# GPS.net
KiCad netlist of a schematic drawn in Altium Designer
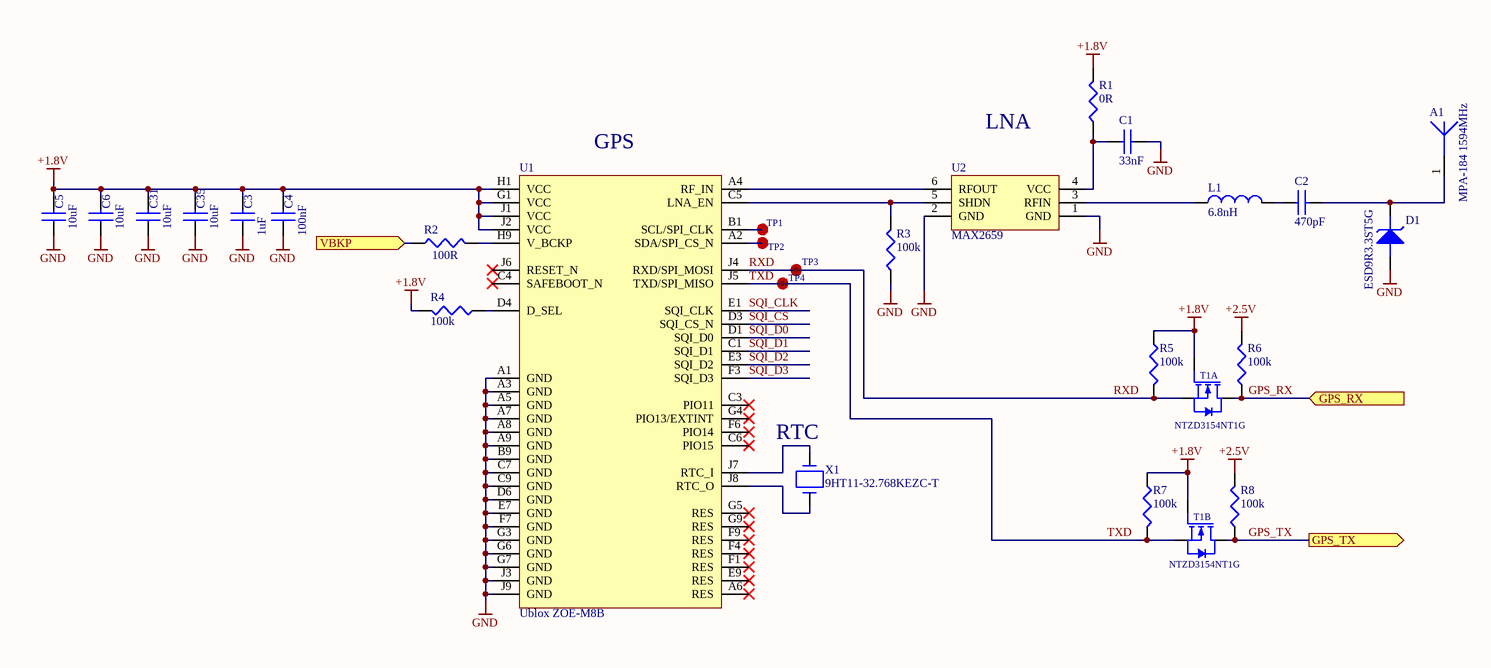
[diagram p0: GPS.SchDoc]

(export (version "E")
  (design (tool "Eeschema 10.0.6"))
  (components
    (comp (ref "A1")
      (value "MPA-184 1594MHz")
      (footprint "MPA-184")
      (description "Antennas Passive GPS/GLONASS Patch Antenna")
      (fields (field (name "MANUFACTURER") "Antenova") (field (name "MANUFACTURER PART NUMBER") "SR42I010-R"))
      (libsource (lib "Passive") (part "ANT - MAXTENA MPA-184 1594MHz"))
    )
    (comp (ref "C1")
      (value "33nF")
      (footprint "CAP0402")
      (fields
        (field (name "MANUFACTURER") "Multicomp")
        (field (name "MANUFACTURER PART NUMBER") "MC0402N330J160CT")
        (field (name "TOLERANCE") "5%")
      )
      (libsource (lib "Passive") (part "C - 33pF/0402"))
    )
    (comp (ref "C2")
      (value "470pF")
      (footprint "CAP0402")
      (fields
        (field (name "MANUFACTURER") "Murata")
        (field (name "MANUFACTURER PART NUMBER") "GRT155R71H471KE01D")
        (field (name "IRNAS PART NO.") "/")
      )
      (libsource (lib "Passive") (part "C - 470pF/0402"))
    )
    (comp (ref "C3")
      (value "1uF")
      (footprint "CAP0402")
      (description "CAP CER 1UF 10V 20% X5R 0402")
      (fields
        (field (name "MANUFACTURER") "Murata")
        (field (name "MANUFACTURER PART NUMBER") "GRM155R61A105ME15D")
      )
      (libsource (lib "Passive") (part "C - 1uF/0402"))
    )
    (comp (ref "C4")
      (value "100nF")
      (footprint "CAP0402")
      (fields
        (field (name "MANUFACTURER") "Multicomp")
        (field (name "MANUFACTURER PART NUMBER") "MC0402X104J160CT")
        (field (name "TOLERANCE") "5%")
      )
      (libsource (lib "Passive") (part "C - 100nF/0402"))
    )
    (comp (ref "C5")
      (value "10uF")
      (footprint "CAP0603")
      (description "10uf/0603/20%")
      (fields
        (field (name "MANUFACTURER") "KEMET")
        (field (name "MANUFACTURER PART NUMBER") "C0603C106M8PACTU")
      )
      (libsource (lib "pira-smart-schlib") (part "10uF"))
    )
    (comp (ref "C6")
      (value "10uF")
      (footprint "CAP0603")
      (description "10uf/0603/20%")
      (fields
        (field (name "MANUFACTURER") "KEMET")
        (field (name "MANUFACTURER PART NUMBER") "C0603C106M8PACTU")
      )
      (libsource (lib "pira-smart-schlib") (part "10uF"))
    )
    (comp (ref "C31")
      (value "10uF")
      (footprint "CAP0603")
      (description "10uf/0603/20%")
      (fields
        (field (name "MANUFACTURER") "KEMET")
        (field (name "MANUFACTURER PART NUMBER") "C0603C106M8PACTU")
      )
      (libsource (lib "pira-smart-schlib") (part "10uF"))
    )
    (comp (ref "C35")
      (value "10uF")
      (footprint "CAP0603")
      (description "10uf/0603/20%")
      (fields
        (field (name "MANUFACTURER") "KEMET")
        (field (name "MANUFACTURER PART NUMBER") "C0603C106M8PACTU")
      )
      (libsource (lib "pira-smart-schlib") (part "10uF"))
    )
    (comp (ref "D1")
      (value "ESD9R3.3ST5G")
      (footprint "SOD-923")
      (description "TVS Diode, ESD9R Series, Unidirectional, 3.3 V, 7.8 V")
      (fields
        (field (name "MANUFACTURER") "DIODES INC.")
        (field (name "MANUFACTURER PART NUMBER") "1N4148W-7-F.")
      )
      (libsource (lib "Active") (part "D_TVS - ESD9R3.3ST5G"))
    )
    (comp (ref "L1")
      (value "6.8nH")
      (footprint "IND0402")
      (description "FIXED IND 33NH 200MA 580 MOHM")
      (fields
        (field (name "MANUFACTURER") "Murata")
        (field (name "MANUFACTURER PART NUMBER") "LQG15HS33NJ02D")
      )
      (libsource (lib "Passive") (part "L - 33nH/0402"))
    )
    (comp (ref "R1")
      (value "0R")
      (footprint "RES0402")
      (description "RESISTOR, 0402, 0R, ANTI SULFURATION")
      (fields
        (field (name "MANUFACTURER") "Multicomp")
        (field (name "MANUFACTURER PART NUMBER") "MCMR04X000PTL")
      )
      (libsource (lib "Passive") (part "R - 0R/0402"))
    )
    (comp (ref "R2")
      (value "100R")
      (footprint "RES0402")
      (fields
        (field (name "MANUFACTURER") "Multicomp")
        (field (name "MANUFACTURER PART NUMBER") "MCMR04X1000FTL")
        (field (name "TOLERANCE") "1%")
      )
      (libsource (lib "Passive") (part "R - 100R/0402"))
    )
    (comp (ref "R3")
      (value "100k")
      (footprint "RES0402")
      (description "MULTICOMP   MCWR04X1003FTL   RES, THICK FILM, 100KOHM, 1%, 0.0625W")
      (fields
        (field (name "MANUFACTURER") "Multicomp")
        (field (name "MANUFACTURER PART NUMBER") "MCWR04X1003FTL")
      )
      (libsource (lib "Passive") (part "R - 100k/0402"))
    )
    (comp (ref "R4")
      (value "100k")
      (footprint "RES0402")
      (description "MULTICOMP   MCWR04X1003FTL   RES, THICK FILM, 100KOHM, 1%, 0.0625W")
      (fields
        (field (name "MANUFACTURER") "Multicomp")
        (field (name "MANUFACTURER PART NUMBER") "MCWR04X1003FTL")
      )
      (libsource (lib "Passive") (part "R - 100k/0402"))
    )
    (comp (ref "R5")
      (value "100k")
      (footprint "RES0402")
      (description "MULTICOMP   MCWR04X1003FTL   RES, THICK FILM, 100KOHM, 1%, 0.0625W")
      (fields
        (field (name "MANUFACTURER") "Multicomp")
        (field (name "MANUFACTURER PART NUMBER") "MCWR04X1003FTL")
      )
      (libsource (lib "Passive") (part "R - 100k/0402"))
    )
    (comp (ref "R6")
      (value "100k")
      (footprint "RES0402")
      (description "MULTICOMP   MCWR04X1003FTL   RES, THICK FILM, 100KOHM, 1%, 0.0625W")
      (fields
        (field (name "MANUFACTURER") "Multicomp")
        (field (name "MANUFACTURER PART NUMBER") "MCWR04X1003FTL")
      )
      (libsource (lib "Passive") (part "R - 100k/0402"))
    )
    (comp (ref "R7")
      (value "100k")
      (footprint "RES0402")
      (description "MULTICOMP   MCWR04X1003FTL   RES, THICK FILM, 100KOHM, 1%, 0.0625W")
      (fields
        (field (name "MANUFACTURER") "Multicomp")
        (field (name "MANUFACTURER PART NUMBER") "MCWR04X1003FTL")
      )
      (libsource (lib "Passive") (part "R - 100k/0402"))
    )
    (comp (ref "R8")
      (value "100k")
      (footprint "RES0402")
      (description "MULTICOMP   MCWR04X1003FTL   RES, THICK FILM, 100KOHM, 1%, 0.0625W")
      (fields
        (field (name "MANUFACTURER") "Multicomp")
        (field (name "MANUFACTURER PART NUMBER") "MCWR04X1003FTL")
      )
      (libsource (lib "Passive") (part "R - 100k/0402"))
    )
    (comp (ref "T1")
      (value "NTZD3154NT1G")
      (footprint "SOT-563")
      (description "Dual MOSFET, Dual N Channel, 540 mA, 20 V, 0.4 ohm, 4.5 V, 1 V")
      (fields (field (name "AUTHOR") "Ciril Golob"))
      (libsource (lib "Active") (part "T_M - NTZD3154NT1G"))
    )
    (comp (ref "TP1")
      (value "TestPoint")
      (footprint "Passive:TestPoint:1.2x1.2mm")
      (description "TEST POINT ROUND SMD")
      (libsource (lib "Passive") (part "TestPoint"))
    )
    (comp (ref "TP2")
      (value "TestPoint")
      (footprint "Passive:TestPoint:1.2x1.2mm")
      (description "TEST POINT ROUND SMD")
      (libsource (lib "Passive") (part "TestPoint"))
    )
    (comp (ref "TP3")
      (value "TestPoint")
      (footprint "Passive:TestPoint:1.2x1.2mm")
      (description "TEST POINT ROUND SMD")
      (libsource (lib "Passive") (part "TestPoint"))
    )
    (comp (ref "TP4")
      (value "TestPoint")
      (footprint "Passive:TestPoint:1.2x1.2mm")
      (description "TEST POINT ROUND SMD")
      (libsource (lib "Passive") (part "TestPoint"))
    )
    (comp (ref "U1")
      (value "Ublox ZOE-M8B")
      (footprint "S-LGA51")
      (description "ZOE-M8 RF Receiver BeiDou, Galileo, GLONASS, GNSS, GPS -160dBm")
      (fields (field (name "MANUFACTURER") "u-blox") (field (name "MANUFACTURER PART NUMBER") "MAX-M8Q-0"))
      (libsource (lib "Active") (part "RF - UBLOX-ZOE-M8B"))
    )
    (comp (ref "U2")
      (value "MAX2659")
      (footprint "uDFN-6")
      (description "RF Amplifier, GPS / GNSS, 20.5 dB Gain / 0.8 dB Noise, 1575.42 MHz, 1.6 V to 3.3 V Supply")
      (fields (field (name "MANUFACTURER") "u-blox") (field (name "MANUFACTURER PART NUMBER") "MAX-M8Q-0"))
      (libsource (lib "Active") (part "RF - MAX2659"))
    )
    (comp (ref "X1")
      (value "9HT11-32.768KEZC-T")
      (footprint "9HT11")
      (description "Crystal, 32.768 kHz, SMD, 2mm x 1.2mm, 9 pF, 10 ppm, 9HT11 Series")
      (fields (field (name "MANUFACTURER") "IQD") (field (name "MANUFACTURER PART NUMBER") "LFXTAL009678"))
      (libsource (lib "Passive") (part "X - 9HT11-32.768KEZC-T"))
    )
  )
  (nets
    (net (code "1") (name "+1.8V") (class "Default")
      (node (ref "C3") (pin "2") (pinfunction "2_2") (pintype "passive"))
      (node (ref "C31") (pin "2") (pinfunction "2_2") (pintype "passive"))
      (node (ref "C35") (pin "2") (pinfunction "2_2") (pintype "passive"))
      (node (ref "C4") (pin "2") (pinfunction "2_2") (pintype "passive"))
      (node (ref "C5") (pin "2") (pinfunction "2_2") (pintype "passive"))
      (node (ref "C6") (pin "2") (pinfunction "2_2") (pintype "passive"))
      (node (ref "R1") (pin "2") (pinfunction "2_2") (pintype "passive"))
      (node (ref "R4") (pin "2") (pinfunction "2_2") (pintype "passive"))
      (node (ref "R5") (pin "1") (pinfunction "1_1") (pintype "passive"))
      (node (ref "R7") (pin "1") (pinfunction "1_1") (pintype "passive"))
      (node (ref "T1") (pin "2") (pinfunction "G1_2") (pintype "passive"))
      (node (ref "T1") (pin "5") (pinfunction "G2_5") (pintype "passive"))
      (node (ref "U1") (pin "G1") (pinfunction "VCC_G1") (pintype "passive"))
      (node (ref "U1") (pin "H1") (pinfunction "VCC_H1") (pintype "passive"))
      (node (ref "U1") (pin "J1") (pinfunction "VCC_J1") (pintype "passive"))
      (node (ref "U1") (pin "J2") (pinfunction "VCC_J2") (pintype "passive"))
    )
    (net (code "2") (name "+2.5V") (class "Default")
      (node (ref "R6") (pin "2") (pinfunction "2_2") (pintype "passive"))
      (node (ref "R8") (pin "2") (pinfunction "2_2") (pintype "passive"))
    )
    (net (code "3") (name "/GPS_RX") (class "Default")
      (node (ref "R6") (pin "1") (pinfunction "1_1") (pintype "passive"))
      (node (ref "T1") (pin "6") (pinfunction "D1_6") (pintype "passive"))
    )
    (net (code "4") (name "/GPS_TX") (class "Default")
      (node (ref "R8") (pin "1") (pinfunction "1_1") (pintype "passive"))
      (node (ref "T1") (pin "3") (pinfunction "D2_3") (pintype "passive"))
    )
    (net (code "5") (name "/RXD") (class "Default")
      (node (ref "R5") (pin "2") (pinfunction "2_2") (pintype "passive"))
      (node (ref "T1") (pin "1") (pinfunction "S1_1") (pintype "passive"))
      (node (ref "TP3") (pin "0") (pinfunction "0_0") (pintype "passive"))
      (node (ref "U1") (pin "J4") (pinfunction "RXD/SPI_MOSI_J4") (pintype "passive"))
    )
    (net (code "6") (name "/SQI_CLK") (class "Default")
      (node (ref "U1") (pin "E1") (pinfunction "SQI_CLK_E1") (pintype "passive"))
    )
    (net (code "7") (name "/SQI_CS") (class "Default")
      (node (ref "U1") (pin "D3") (pinfunction "SQI_CS_N_D3") (pintype "passive"))
    )
    (net (code "8") (name "/SQI_D0") (class "Default")
      (node (ref "U1") (pin "D1") (pinfunction "SQI_D0_D1") (pintype "passive"))
    )
    (net (code "9") (name "/SQI_D1") (class "Default")
      (node (ref "U1") (pin "C1") (pinfunction "SQI_D1_C1") (pintype "passive"))
    )
    (net (code "10") (name "/SQI_D2") (class "Default")
      (node (ref "U1") (pin "E3") (pinfunction "SQI_D2_E3") (pintype "passive"))
    )
    (net (code "11") (name "/SQI_D3") (class "Default")
      (node (ref "U1") (pin "F3") (pinfunction "SQI_D3_F3") (pintype "passive"))
    )
    (net (code "12") (name "/TXD") (class "Default")
      (node (ref "R7") (pin "2") (pinfunction "2_2") (pintype "passive"))
      (node (ref "T1") (pin "4") (pinfunction "S2_4") (pintype "passive"))
      (node (ref "TP4") (pin "0") (pinfunction "0_0") (pintype "passive"))
      (node (ref "U1") (pin "J5") (pinfunction "TXD/SPI_MISO_J5") (pintype "passive"))
    )
    (net (code "13") (name "/VBKP") (class "Default")
      (node (ref "R2") (pin "1") (pinfunction "1_1") (pintype "passive"))
    )
    (net (code "14") (name "GND") (class "Default")
      (node (ref "C1") (pin "1") (pinfunction "1_1") (pintype "passive"))
      (node (ref "C3") (pin "1") (pinfunction "1_1") (pintype "passive"))
      (node (ref "C31") (pin "1") (pinfunction "1_1") (pintype "passive"))
      (node (ref "C35") (pin "1") (pinfunction "1_1") (pintype "passive"))
      (node (ref "C4") (pin "1") (pinfunction "1_1") (pintype "passive"))
      (node (ref "C5") (pin "1") (pinfunction "1_1") (pintype "passive"))
      (node (ref "C6") (pin "1") (pinfunction "1_1") (pintype "passive"))
      (node (ref "D1") (pin "A") (pinfunction "ANODE_A") (pintype "passive"))
      (node (ref "R3") (pin "1") (pinfunction "1_1") (pintype "passive"))
      (node (ref "U1") (pin "A1") (pinfunction "GND_A1") (pintype "passive"))
      (node (ref "U1") (pin "A3") (pinfunction "GND_A3") (pintype "passive"))
      (node (ref "U1") (pin "A5") (pinfunction "GND_A5") (pintype "passive"))
      (node (ref "U1") (pin "A7") (pinfunction "GND_A7") (pintype "passive"))
      (node (ref "U1") (pin "A8") (pinfunction "GND_A8") (pintype "passive"))
      (node (ref "U1") (pin "A9") (pinfunction "GND_A9") (pintype "passive"))
      (node (ref "U1") (pin "B9") (pinfunction "GND_B9") (pintype "passive"))
      (node (ref "U1") (pin "C7") (pinfunction "GND_C7") (pintype "passive"))
      (node (ref "U1") (pin "C9") (pinfunction "GND_C9") (pintype "passive"))
      (node (ref "U1") (pin "D6") (pinfunction "GND_D6") (pintype "passive"))
      (node (ref "U1") (pin "E7") (pinfunction "GND_E7") (pintype "passive"))
      (node (ref "U1") (pin "F7") (pinfunction "GND_F7") (pintype "passive"))
      (node (ref "U1") (pin "G3") (pinfunction "GND_G3") (pintype "passive"))
      (node (ref "U1") (pin "G6") (pinfunction "GND_G6") (pintype "passive"))
      (node (ref "U1") (pin "G7") (pinfunction "GND_G7") (pintype "passive"))
      (node (ref "U1") (pin "J3") (pinfunction "GND_J3") (pintype "passive"))
      (node (ref "U1") (pin "J9") (pinfunction "GND_J9") (pintype "passive"))
      (node (ref "U2") (pin "1") (pinfunction "GND_1") (pintype "passive"))
      (node (ref "U2") (pin "2") (pinfunction "GND_2") (pintype "passive"))
    )
    (net (code "15") (name "Net-(A1-ANT)") (class "Default")
      (node (ref "A1") (pin "1") (pinfunction "ANT_1") (pintype "passive"))
      (node (ref "C2") (pin "2") (pinfunction "2_2") (pintype "passive"))
      (node (ref "D1") (pin "K") (pinfunction "cathode_K") (pintype "passive"))
    )
    (net (code "16") (name "Net-(C2-Pad1)") (class "Default")
      (node (ref "C2") (pin "1") (pinfunction "1_1") (pintype "passive"))
      (node (ref "L1") (pin "2") (pinfunction "2_2") (pintype "passive"))
    )
    (net (code "17") (name "Net-(U1-D_SEL)") (class "Default")
      (node (ref "R4") (pin "1") (pinfunction "1_1") (pintype "passive"))
      (node (ref "U1") (pin "D4") (pinfunction "D_SEL_D4") (pintype "passive"))
    )
    (net (code "18") (name "Net-(U1-LNA_EN)") (class "Default")
      (node (ref "R3") (pin "2") (pinfunction "2_2") (pintype "passive"))
      (node (ref "U1") (pin "C5") (pinfunction "LNA_EN_C5") (pintype "passive"))
      (node (ref "U2") (pin "5") (pinfunction "SHDN_5") (pintype "passive"))
    )
    (net (code "19") (name "Net-(U1-RF_IN)") (class "Default")
      (node (ref "U1") (pin "A4") (pinfunction "RF_IN_A4") (pintype "passive"))
      (node (ref "U2") (pin "6") (pinfunction "RFOUT_6") (pintype "passive"))
    )
    (net (code "20") (name "Net-(U1-RTC_I)") (class "Default")
      (node (ref "U1") (pin "J7") (pinfunction "RTC_I_J7") (pintype "passive"))
      (node (ref "X1") (pin "2") (pinfunction "2_2") (pintype "passive"))
    )
    (net (code "21") (name "Net-(U1-RTC_O)") (class "Default")
      (node (ref "U1") (pin "J8") (pinfunction "RTC_O_J8") (pintype "passive"))
      (node (ref "X1") (pin "1") (pinfunction "1_1") (pintype "passive"))
    )
    (net (code "22") (name "Net-(U1-SCL{slash}SPI_CLK)") (class "Default")
      (node (ref "TP1") (pin "0") (pinfunction "0_0") (pintype "passive"))
      (node (ref "U1") (pin "B1") (pinfunction "SCL/SPI_CLK_B1") (pintype "passive"))
    )
    (net (code "23") (name "Net-(U1-SDA{slash}SPI_CS_N)") (class "Default")
      (node (ref "TP2") (pin "0") (pinfunction "0_0") (pintype "passive"))
      (node (ref "U1") (pin "A2") (pinfunction "SDA/SPI_CS_N_A2") (pintype "passive"))
    )
    (net (code "24") (name "Net-(U1-V_BCKP)") (class "Default")
      (node (ref "R2") (pin "2") (pinfunction "2_2") (pintype "passive"))
      (node (ref "U1") (pin "H9") (pinfunction "V_BCKP_H9") (pintype "passive"))
    )
    (net (code "25") (name "Net-(U2-RFIN)") (class "Default")
      (node (ref "L1") (pin "1") (pinfunction "1_1") (pintype "passive"))
      (node (ref "U2") (pin "3") (pinfunction "RFIN_3") (pintype "passive"))
    )
    (net (code "26") (name "Net-(U2-VCC)") (class "Default")
      (node (ref "C1") (pin "2") (pinfunction "2_2") (pintype "passive"))
      (node (ref "R1") (pin "1") (pinfunction "1_1") (pintype "passive"))
      (node (ref "U2") (pin "4") (pinfunction "VCC_4") (pintype "passive"))
    )
    (net (code "27") (name "unconnected-(U1-PIO11-PadC3)") (class "Default")
      (node (ref "U1") (pin "C3") (pinfunction "PIO11_C3") (pintype "passive+no_connect"))
    )
    (net (code "28") (name "unconnected-(U1-PIO13{slash}EXTINT-PadG4)") (class "Default")
      (node (ref "U1") (pin "G4") (pinfunction "PIO13/EXTINT_G4") (pintype "passive+no_connect"))
    )
    (net (code "29") (name "unconnected-(U1-PIO14-PadF6)") (class "Default")
      (node (ref "U1") (pin "F6") (pinfunction "PIO14_F6") (pintype "passive+no_connect"))
    )
    (net (code "30") (name "unconnected-(U1-PIO15-PadC6)") (class "Default")
      (node (ref "U1") (pin "C6") (pinfunction "PIO15_C6") (pintype "passive+no_connect"))
    )
    (net (code "31") (name "unconnected-(U1-RES-PadA6)") (class "Default")
      (node (ref "U1") (pin "A6") (pinfunction "RES_A6") (pintype "passive+no_connect"))
    )
    (net (code "32") (name "unconnected-(U1-RES-PadE9)") (class "Default")
      (node (ref "U1") (pin "E9") (pinfunction "RES_E9") (pintype "passive+no_connect"))
    )
    (net (code "33") (name "unconnected-(U1-RES-PadF1)") (class "Default")
      (node (ref "U1") (pin "F1") (pinfunction "RES_F1") (pintype "passive+no_connect"))
    )
    (net (code "34") (name "unconnected-(U1-RES-PadF4)") (class "Default")
      (node (ref "U1") (pin "F4") (pinfunction "RES_F4") (pintype "passive+no_connect"))
    )
    (net (code "35") (name "unconnected-(U1-RES-PadF9)") (class "Default")
      (node (ref "U1") (pin "F9") (pinfunction "RES_F9") (pintype "passive+no_connect"))
    )
    (net (code "36") (name "unconnected-(U1-RES-PadG5)") (class "Default")
      (node (ref "U1") (pin "G5") (pinfunction "RES_G5") (pintype "passive+no_connect"))
    )
    (net (code "37") (name "unconnected-(U1-RES-PadG9)") (class "Default")
      (node (ref "U1") (pin "G9") (pinfunction "RES_G9") (pintype "passive+no_connect"))
    )
    (net (code "38") (name "unconnected-(U1-RESET_N-PadJ6)") (class "Default")
      (node (ref "U1") (pin "J6") (pinfunction "RESET_N_J6") (pintype "passive+no_connect"))
    )
    (net (code "39") (name "unconnected-(U1-SAFEBOOT_N-PadC4)") (class "Default")
      (node (ref "U1") (pin "C4") (pinfunction "SAFEBOOT_N_C4") (pintype "passive+no_connect"))
    )
  )
)
